# FPGA.net
KiCad netlist of a schematic drawn in Altium Designer
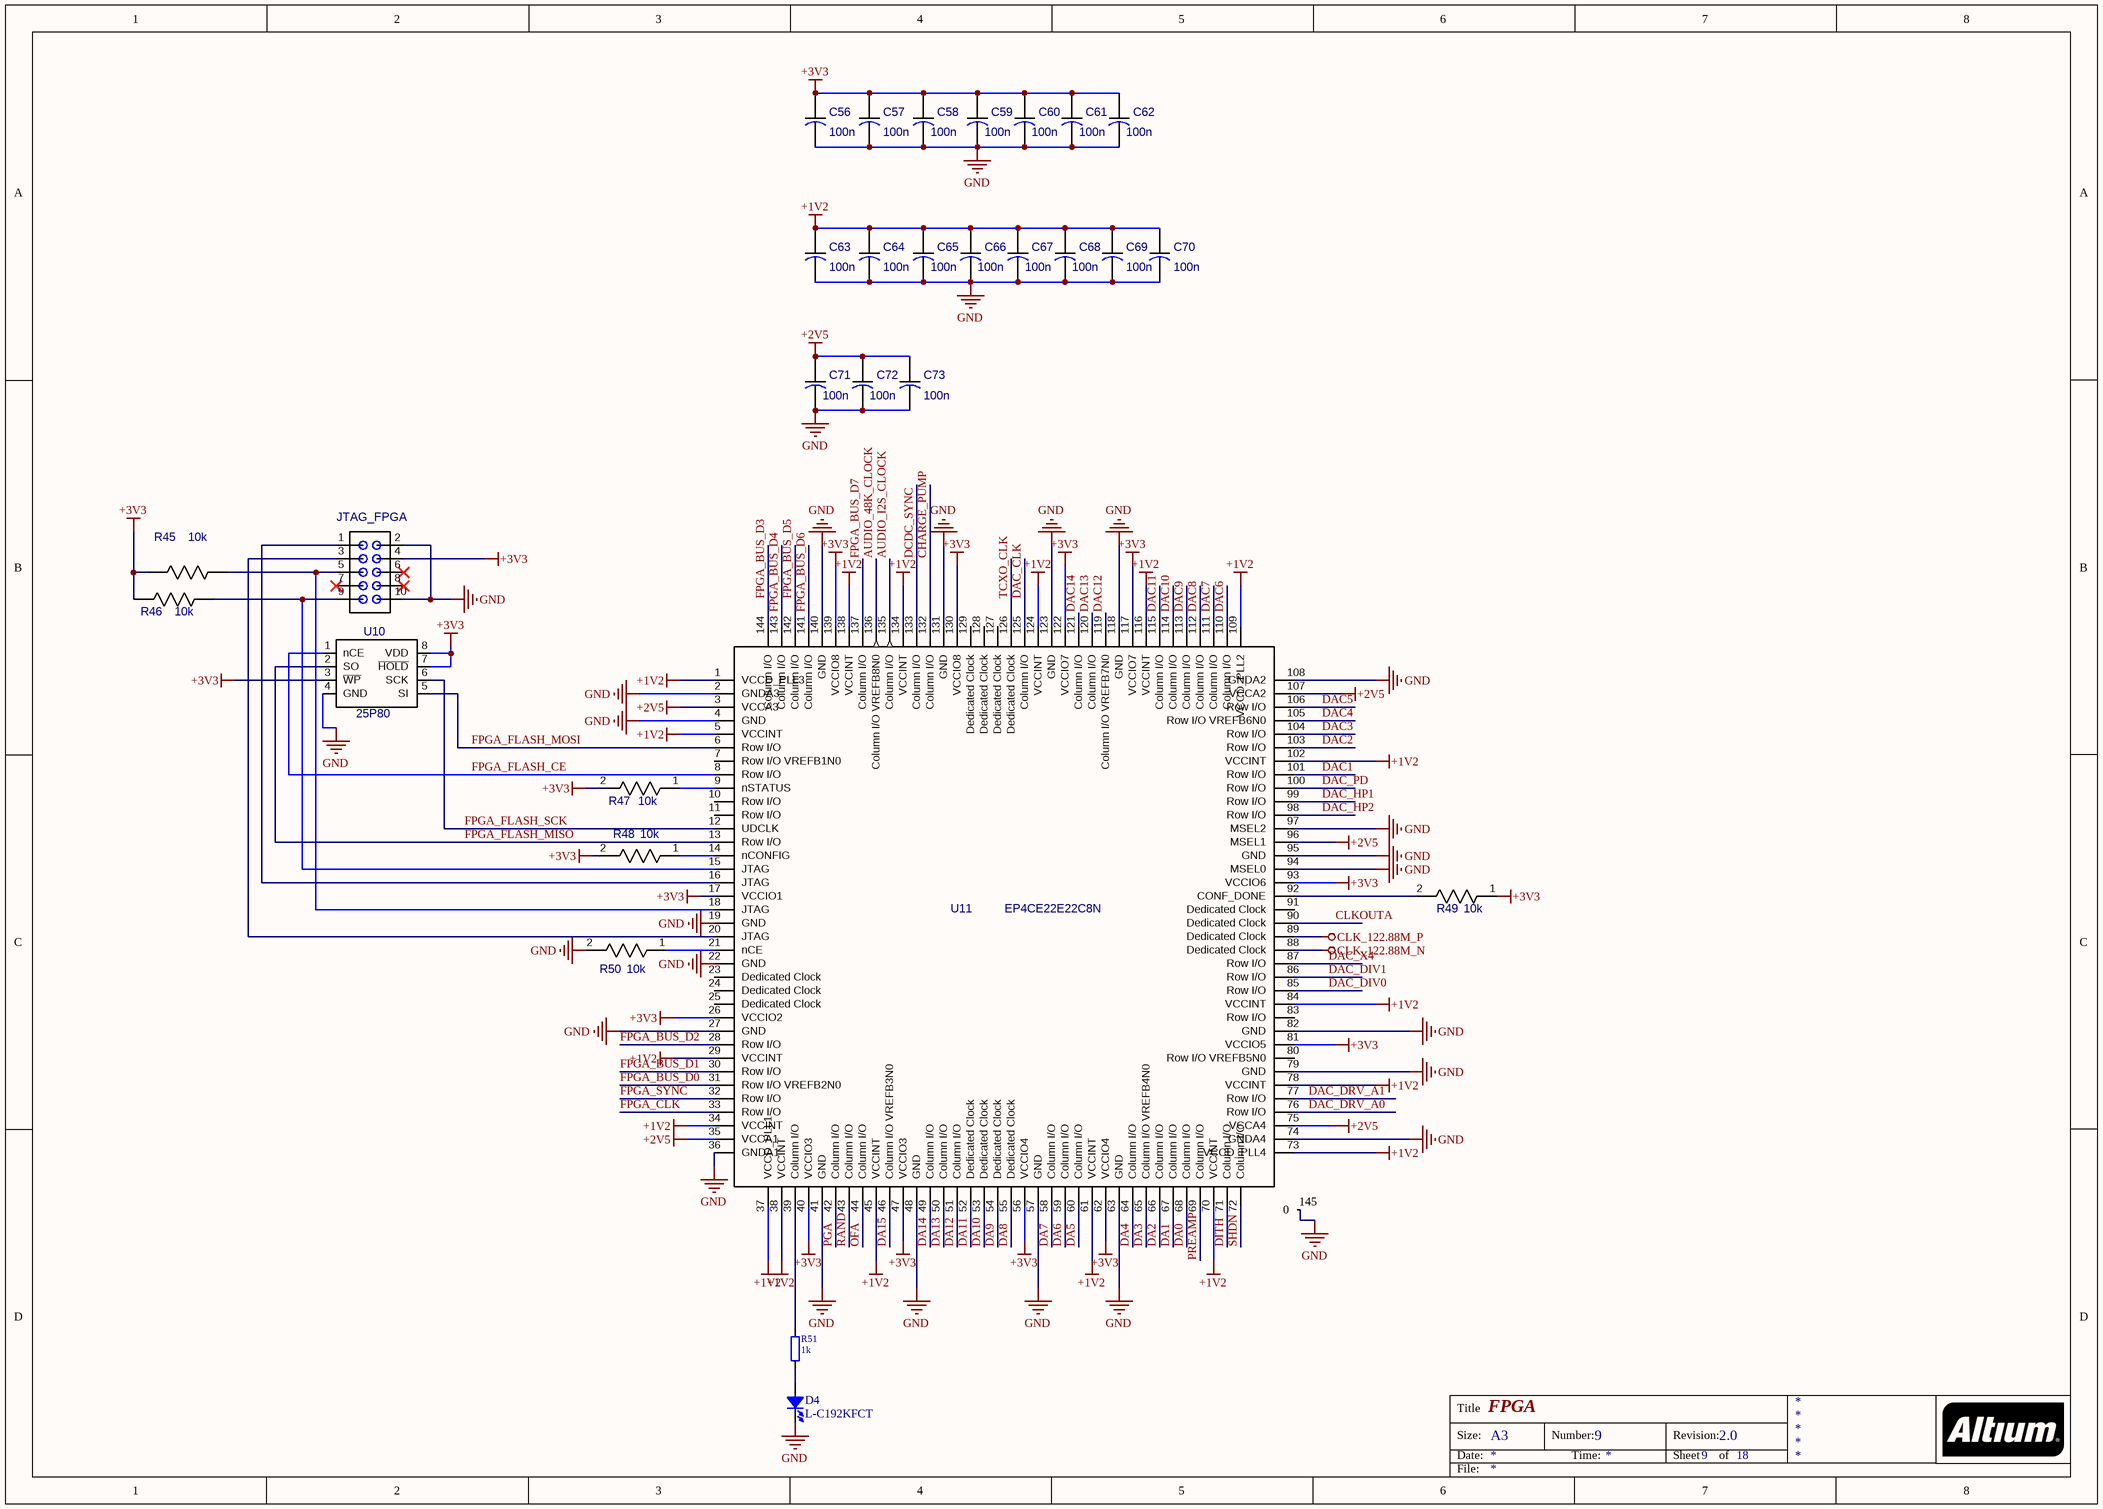
[diagram p0: FPGA.SchDoc]

(export (version "E")
  (design (tool "Eeschema 10.0.6"))
  (components
    (comp (ref "C56")
      (value "100n")
      (footprint "CAP_0805")
      (description "CAP_0805")
      (libsource (lib "*") (part "CAP_0805"))
    )
    (comp (ref "C57")
      (value "100n")
      (footprint "CAP_0805")
      (description "CAP_0805")
      (libsource (lib "*") (part "CAP_0805"))
    )
    (comp (ref "C58")
      (value "100n")
      (footprint "CAP_0805")
      (description "CAP_0805")
      (libsource (lib "*") (part "CAP_0805"))
    )
    (comp (ref "C59")
      (value "100n")
      (footprint "CAP_0805")
      (description "CAP_0805")
      (libsource (lib "*") (part "CAP_0805"))
    )
    (comp (ref "C60")
      (value "100n")
      (footprint "CAP_0805")
      (description "CAP_0805")
      (libsource (lib "*") (part "CAP_0805"))
    )
    (comp (ref "C61")
      (value "100n")
      (footprint "CAP_0805")
      (description "CAP_0805")
      (libsource (lib "*") (part "CAP_0805"))
    )
    (comp (ref "C62")
      (value "100n")
      (footprint "CAP_0805")
      (description "CAP_0805")
      (libsource (lib "*") (part "CAP_0805"))
    )
    (comp (ref "C63")
      (value "100n")
      (footprint "CAP_0805")
      (description "CAP_0805")
      (libsource (lib "*") (part "CAP_0805"))
    )
    (comp (ref "C64")
      (value "100n")
      (footprint "CAP_0805")
      (description "CAP_0805")
      (libsource (lib "*") (part "CAP_0805"))
    )
    (comp (ref "C65")
      (value "100n")
      (footprint "CAP_0805")
      (description "CAP_0805")
      (libsource (lib "*") (part "CAP_0805"))
    )
    (comp (ref "C66")
      (value "100n")
      (footprint "CAP_0805")
      (description "CAP_0805")
      (libsource (lib "*") (part "CAP_0805"))
    )
    (comp (ref "C67")
      (value "100n")
      (footprint "CAP_0805")
      (description "CAP_0805")
      (libsource (lib "*") (part "CAP_0805"))
    )
    (comp (ref "C68")
      (value "100n")
      (footprint "CAP_0805")
      (description "CAP_0805")
      (libsource (lib "*") (part "CAP_0805"))
    )
    (comp (ref "C69")
      (value "100n")
      (footprint "CAP_0805")
      (description "CAP_0805")
      (libsource (lib "*") (part "CAP_0805"))
    )
    (comp (ref "C70")
      (value "100n")
      (footprint "CAP_0805")
      (description "CAP_0805")
      (libsource (lib "*") (part "CAP_0805"))
    )
    (comp (ref "C71")
      (value "100n")
      (footprint "CAP_0805")
      (description "CAP_0805")
      (libsource (lib "*") (part "CAP_0805"))
    )
    (comp (ref "C72")
      (value "100n")
      (footprint "CAP_0805")
      (description "CAP_0805")
      (libsource (lib "*") (part "CAP_0805"))
    )
    (comp (ref "C73")
      (value "100n")
      (footprint "CAP_0805")
      (description "CAP_0805")
      (libsource (lib "*") (part "CAP_0805"))
    )
    (comp (ref "D4")
      (value "L-C192KFCT")
      (footprint "LED 0603")
      (description "SMD LED Diode")
      (fields (field (name "MANUFACTURER") "Paralight"))
      (libsource (lib "Hristo") (part "D LED"))
    )
    (comp (ref "JTAG_FPGA")
      (value "~")
      (footprint "IDC10")
      (description "2*5 Pin")
      (libsource (lib "*") (part "IDC10"))
    )
    (comp (ref "R45")
      (value "10k")
      (footprint "RES_0805")
      (description "RES_0805")
      (libsource (lib "") (part "RES_0805_1"))
    )
    (comp (ref "R46")
      (value "10k")
      (footprint "RES_0805")
      (description "RES_0805")
      (libsource (lib "") (part "RES_0805_1"))
    )
    (comp (ref "R47")
      (value "10k")
      (footprint "RES_0805")
      (description "RES_0805")
      (libsource (lib "*") (part "RES_0805"))
    )
    (comp (ref "R48")
      (value "10k")
      (footprint "RES_0805")
      (description "RES_0805")
      (libsource (lib "*") (part "RES_0805"))
    )
    (comp (ref "R49")
      (value "10k")
      (footprint "RES_0805")
      (description "RES_0805")
      (libsource (lib "*") (part "RES_0805"))
    )
    (comp (ref "R50")
      (value "10k")
      (footprint "RES_0805")
      (description "RES_0805")
      (libsource (lib "*") (part "RES_0805"))
    )
    (comp (ref "R51")
      (value "1k")
      (footprint "R-0603")
      (description "Chip Resistor")
      (fields (field (name "MANUFACTURER") "Yageo/Phycomp"))
      (libsource (lib "Hristo") (part "RES semi"))
    )
    (comp (ref "U10") (value "25P80") (footprint "25P80") (libsource (lib "*") (part "25P80")))
    (comp (ref "U11")
      (value "EP4CE22E22C8N")
      (footprint "QFP144-20-2222A")
      (libsource (lib "*") (part "EP4CE22E22C8N"))
    )
  )
  (nets
    (net (code "1") (name "+1V2") (class "Default")
      (node (ref "C63") (pin "1") (pinfunction "1_1") (pintype "passive"))
      (node (ref "C64") (pin "1") (pinfunction "1_1") (pintype "passive"))
      (node (ref "C65") (pin "1") (pinfunction "1_1") (pintype "passive"))
      (node (ref "C66") (pin "1") (pinfunction "1_1") (pintype "passive"))
      (node (ref "C67") (pin "1") (pinfunction "1_1") (pintype "passive"))
      (node (ref "C68") (pin "1") (pinfunction "1_1") (pintype "passive"))
      (node (ref "C69") (pin "1") (pinfunction "1_1") (pintype "passive"))
      (node (ref "C70") (pin "1") (pinfunction "1_1") (pintype "passive"))
      (node (ref "U11") (pin "1") (pinfunction "VCCD_PLL3_1") (pintype "passive"))
      (node (ref "U11") (pin "102") (pinfunction "VCCINT_102") (pintype "passive"))
      (node (ref "U11") (pin "109") (pinfunction "VCCD_PLL2_109") (pintype "passive"))
      (node (ref "U11") (pin "116") (pinfunction "VCCINT_116") (pintype "passive"))
      (node (ref "U11") (pin "124") (pinfunction "VCCINT_124") (pintype "passive"))
      (node (ref "U11") (pin "134") (pinfunction "VCCINT_134") (pintype "passive"))
      (node (ref "U11") (pin "138") (pinfunction "VCCINT_138") (pintype "passive"))
      (node (ref "U11") (pin "29") (pinfunction "VCCINT_29") (pintype "passive"))
      (node (ref "U11") (pin "34") (pinfunction "VCCINT_34") (pintype "passive"))
      (node (ref "U11") (pin "37") (pinfunction "VCCD_PLL1_37") (pintype "passive"))
      (node (ref "U11") (pin "38") (pinfunction "VCCINT_38") (pintype "passive"))
      (node (ref "U11") (pin "45") (pinfunction "VCCINT_45") (pintype "passive"))
      (node (ref "U11") (pin "5") (pinfunction "VCCINT_5") (pintype "passive"))
      (node (ref "U11") (pin "61") (pinfunction "VCCINT_61") (pintype "passive"))
      (node (ref "U11") (pin "70") (pinfunction "VCCINT_70") (pintype "passive"))
      (node (ref "U11") (pin "73") (pinfunction "VCCD_PLL4_73") (pintype "passive"))
      (node (ref "U11") (pin "78") (pinfunction "VCCINT_78") (pintype "passive"))
      (node (ref "U11") (pin "84") (pinfunction "VCCINT_84") (pintype "passive"))
    )
    (net (code "2") (name "+2V5") (class "Default")
      (node (ref "C71") (pin "1") (pinfunction "1_1") (pintype "passive"))
      (node (ref "C72") (pin "1") (pinfunction "1_1") (pintype "passive"))
      (node (ref "C73") (pin "1") (pinfunction "1_1") (pintype "passive"))
      (node (ref "U11") (pin "107") (pinfunction "VCCA2_107") (pintype "passive"))
      (node (ref "U11") (pin "3") (pinfunction "VCCA3_3") (pintype "passive"))
      (node (ref "U11") (pin "35") (pinfunction "VCCA1_35") (pintype "passive"))
      (node (ref "U11") (pin "75") (pinfunction "VCCA4_75") (pintype "passive"))
      (node (ref "U11") (pin "96") (pinfunction "MSEL1_96") (pintype "passive"))
    )
    (net (code "3") (name "+3V3") (class "Default")
      (node (ref "C56") (pin "1") (pinfunction "1_1") (pintype "passive"))
      (node (ref "C57") (pin "1") (pinfunction "1_1") (pintype "passive"))
      (node (ref "C58") (pin "1") (pinfunction "1_1") (pintype "passive"))
      (node (ref "C59") (pin "1") (pinfunction "1_1") (pintype "passive"))
      (node (ref "C60") (pin "1") (pinfunction "1_1") (pintype "passive"))
      (node (ref "C61") (pin "1") (pinfunction "1_1") (pintype "passive"))
      (node (ref "C62") (pin "1") (pinfunction "1_1") (pintype "passive"))
      (node (ref "JTAG_FPGA") (pin "4") (pinfunction "4_4") (pintype "passive"))
      (node (ref "R45") (pin "2") (pinfunction "2_2") (pintype "passive"))
      (node (ref "R46") (pin "2") (pinfunction "2_2") (pintype "passive"))
      (node (ref "R47") (pin "2") (pinfunction "2_2") (pintype "passive"))
      (node (ref "R48") (pin "2") (pinfunction "2_2") (pintype "passive"))
      (node (ref "R49") (pin "1") (pinfunction "1_1") (pintype "passive"))
      (node (ref "U10") (pin "3") (pinfunction "~{WP}_3") (pintype "passive"))
      (node (ref "U10") (pin "7") (pinfunction "~{HOLD}_7") (pintype "passive"))
      (node (ref "U10") (pin "8") (pinfunction "VDD_8") (pintype "passive"))
      (node (ref "U11") (pin "117") (pinfunction "VCCIO7_117") (pintype "passive"))
      (node (ref "U11") (pin "122") (pinfunction "VCCIO7_122") (pintype "passive"))
      (node (ref "U11") (pin "130") (pinfunction "VCCIO8_130") (pintype "passive"))
      (node (ref "U11") (pin "139") (pinfunction "VCCIO8_139") (pintype "passive"))
      (node (ref "U11") (pin "17") (pinfunction "VCCIO1_17") (pintype "passive"))
      (node (ref "U11") (pin "26") (pinfunction "VCCIO2_26") (pintype "passive"))
      (node (ref "U11") (pin "40") (pinfunction "VCCIO3_40") (pintype "passive"))
      (node (ref "U11") (pin "47") (pinfunction "VCCIO3_47") (pintype "passive"))
      (node (ref "U11") (pin "56") (pinfunction "VCCIO4_56") (pintype "passive"))
      (node (ref "U11") (pin "62") (pinfunction "VCCIO4_62") (pintype "passive"))
      (node (ref "U11") (pin "81") (pinfunction "VCCIO5_81") (pintype "passive"))
      (node (ref "U11") (pin "93") (pinfunction "VCCIO6_93") (pintype "passive"))
    )
    (net (code "4") (name "/AUDIO_48K_CLOCK") (class "Default")
      (node (ref "U11") (pin "136") (pinfunction "Column_I/O_VREFB8N0_136") (pintype "output"))
    )
    (net (code "5") (name "/AUDIO_I2S_CLOCK") (class "Default")
      (node (ref "U11") (pin "135") (pinfunction "Column_I/O_135") (pintype "output"))
    )
    (net (code "6") (name "/CHARGE_PUMP") (class "Default")
      (node (ref "U11") (pin "132") (pinfunction "Column_I/O_132") (pintype "passive"))
    )
    (net (code "7") (name "/CLKOUTA") (class "Default")
      (node (ref "U11") (pin "90") (pinfunction "Dedicated_Clock_90") (pintype "passive"))
    )
    (net (code "8") (name "/DA0") (class "Default")
      (node (ref "U11") (pin "68") (pinfunction "Column_I/O_68") (pintype "passive"))
    )
    (net (code "9") (name "/DA1") (class "Default")
      (node (ref "U11") (pin "67") (pinfunction "Column_I/O_67") (pintype "passive"))
    )
    (net (code "10") (name "/DA2") (class "Default")
      (node (ref "U11") (pin "66") (pinfunction "Column_I/O_66") (pintype "passive"))
    )
    (net (code "11") (name "/DA3") (class "Default")
      (node (ref "U11") (pin "65") (pinfunction "Column_I/O_VREFB4N0_65") (pintype "passive"))
    )
    (net (code "12") (name "/DA4") (class "Default")
      (node (ref "U11") (pin "64") (pinfunction "Column_I/O_64") (pintype "passive"))
    )
    (net (code "13") (name "/DA5") (class "Default")
      (node (ref "U11") (pin "60") (pinfunction "Column_I/O_60") (pintype "passive"))
    )
    (net (code "14") (name "/DA6") (class "Default")
      (node (ref "U11") (pin "59") (pinfunction "Column_I/O_59") (pintype "passive"))
    )
    (net (code "15") (name "/DA7") (class "Default")
      (node (ref "U11") (pin "58") (pinfunction "Column_I/O_58") (pintype "passive"))
    )
    (net (code "16") (name "/DA8") (class "Default")
      (node (ref "U11") (pin "55") (pinfunction "Dedicated_Clock_55") (pintype "passive"))
    )
    (net (code "17") (name "/DA9") (class "Default")
      (node (ref "U11") (pin "54") (pinfunction "Dedicated_Clock_54") (pintype "passive"))
    )
    (net (code "18") (name "/DA10") (class "Default")
      (node (ref "U11") (pin "53") (pinfunction "Dedicated_Clock_53") (pintype "passive"))
    )
    (net (code "19") (name "/DA11") (class "Default")
      (node (ref "U11") (pin "52") (pinfunction "Dedicated_Clock_52") (pintype "passive"))
    )
    (net (code "20") (name "/DA12") (class "Default")
      (node (ref "U11") (pin "51") (pinfunction "Column_I/O_51") (pintype "passive"))
    )
    (net (code "21") (name "/DA13") (class "Default")
      (node (ref "U11") (pin "50") (pinfunction "Column_I/O_50") (pintype "passive"))
    )
    (net (code "22") (name "/DA14") (class "Default")
      (node (ref "U11") (pin "49") (pinfunction "Column_I/O_49") (pintype "passive"))
    )
    (net (code "23") (name "/DA15") (class "Default")
      (node (ref "U11") (pin "46") (pinfunction "Column_I/O_VREFB3N0_46") (pintype "passive"))
    )
    (net (code "24") (name "/DAC1") (class "Default")
      (node (ref "U11") (pin "101") (pinfunction "Row_I/O_101") (pintype "passive"))
    )
    (net (code "25") (name "/DAC2") (class "Default")
      (node (ref "U11") (pin "103") (pinfunction "Row_I/O_103") (pintype "passive"))
    )
    (net (code "26") (name "/DAC3") (class "Default")
      (node (ref "U11") (pin "104") (pinfunction "Row_I/O_104") (pintype "passive"))
    )
    (net (code "27") (name "/DAC4") (class "Default")
      (node (ref "U11") (pin "105") (pinfunction "Row_I/O_VREFB6N0_105") (pintype "passive"))
    )
    (net (code "28") (name "/DAC5") (class "Default")
      (node (ref "U11") (pin "106") (pinfunction "Row_I/O_106") (pintype "passive"))
    )
    (net (code "29") (name "/DAC6") (class "Default")
      (node (ref "U11") (pin "110") (pinfunction "Column_I/O_110") (pintype "passive"))
    )
    (net (code "30") (name "/DAC7") (class "Default")
      (node (ref "U11") (pin "111") (pinfunction "Column_I/O_111") (pintype "passive"))
    )
    (net (code "31") (name "/DAC8") (class "Default")
      (node (ref "U11") (pin "112") (pinfunction "Column_I/O_112") (pintype "passive"))
    )
    (net (code "32") (name "/DAC9") (class "Default")
      (node (ref "U11") (pin "113") (pinfunction "Column_I/O_113") (pintype "passive"))
    )
    (net (code "33") (name "/DAC10") (class "Default")
      (node (ref "U11") (pin "114") (pinfunction "Column_I/O_114") (pintype "passive"))
    )
    (net (code "34") (name "/DAC11") (class "Default")
      (node (ref "U11") (pin "115") (pinfunction "Column_I/O_115") (pintype "passive"))
    )
    (net (code "35") (name "/DAC12") (class "Default")
      (node (ref "U11") (pin "119") (pinfunction "Column_I/O_VREFB7N0_119") (pintype "passive"))
    )
    (net (code "36") (name "/DAC13") (class "Default")
      (node (ref "U11") (pin "120") (pinfunction "Column_I/O_120") (pintype "passive"))
    )
    (net (code "37") (name "/DAC14") (class "Default")
      (node (ref "U11") (pin "121") (pinfunction "Column_I/O_121") (pintype "passive"))
    )
    (net (code "38") (name "/DAC_CLK") (class "Default")
      (node (ref "U11") (pin "125") (pinfunction "Column_I/O_125") (pintype "passive"))
    )
    (net (code "39") (name "/DAC_DIV0") (class "Default")
      (node (ref "U11") (pin "85") (pinfunction "Row_I/O_85") (pintype "passive"))
    )
    (net (code "40") (name "/DAC_DIV1") (class "Default")
      (node (ref "U11") (pin "86") (pinfunction "Row_I/O_86") (pintype "passive"))
    )
    (net (code "41") (name "/DAC_DRV_A0") (class "Default")
      (node (ref "U11") (pin "76") (pinfunction "Row_I/O_76") (pintype "passive"))
    )
    (net (code "42") (name "/DAC_DRV_A1") (class "Default")
      (node (ref "U11") (pin "77") (pinfunction "Row_I/O_77") (pintype "passive"))
    )
    (net (code "43") (name "/DAC_HP1") (class "Default")
      (node (ref "U11") (pin "99") (pinfunction "Row_I/O_99") (pintype "passive"))
    )
    (net (code "44") (name "/DAC_HP2") (class "Default")
      (node (ref "U11") (pin "98") (pinfunction "Row_I/O_98") (pintype "passive"))
    )
    (net (code "45") (name "/DAC_PD") (class "Default")
      (node (ref "U11") (pin "100") (pinfunction "Row_I/O_100") (pintype "passive"))
    )
    (net (code "46") (name "/DAC_X4") (class "Default")
      (node (ref "U11") (pin "87") (pinfunction "Row_I/O_87") (pintype "passive"))
    )
    (net (code "47") (name "/DCDC_SYNC") (class "Default")
      (node (ref "U11") (pin "133") (pinfunction "Column_I/O_133") (pintype "passive"))
    )
    (net (code "48") (name "/DITH") (class "Default")
      (node (ref "U11") (pin "71") (pinfunction "Column_I/O_71") (pintype "passive"))
    )
    (net (code "49") (name "/FPGA_BUS_D0") (class "Default")
      (node (ref "U11") (pin "31") (pinfunction "Row_I/O_VREFB2N0_31") (pintype "passive"))
    )
    (net (code "50") (name "/FPGA_BUS_D1") (class "Default")
      (node (ref "U11") (pin "30") (pinfunction "Row_I/O_30") (pintype "passive"))
    )
    (net (code "51") (name "/FPGA_BUS_D2") (class "Default")
      (node (ref "U11") (pin "28") (pinfunction "Row_I/O_28") (pintype "passive"))
    )
    (net (code "52") (name "/FPGA_BUS_D3") (class "Default")
      (node (ref "U11") (pin "144") (pinfunction "Column_I/O_144") (pintype "passive"))
    )
    (net (code "53") (name "/FPGA_BUS_D4") (class "Default")
      (node (ref "U11") (pin "143") (pinfunction "Column_I/O_143") (pintype "passive"))
    )
    (net (code "54") (name "/FPGA_BUS_D5") (class "Default")
      (node (ref "U11") (pin "142") (pinfunction "Column_I/O_142") (pintype "passive"))
    )
    (net (code "55") (name "/FPGA_BUS_D6") (class "Default")
      (node (ref "U11") (pin "141") (pinfunction "Column_I/O_141") (pintype "passive"))
    )
    (net (code "56") (name "/FPGA_BUS_D7") (class "Default")
      (node (ref "U11") (pin "137") (pinfunction "Column_I/O_137") (pintype "passive"))
    )
    (net (code "57") (name "/FPGA_CLK") (class "Default")
      (node (ref "U11") (pin "33") (pinfunction "Row_I/O_33") (pintype "passive"))
    )
    (net (code "58") (name "/FPGA_FLASH_CE") (class "Default")
      (node (ref "U10") (pin "1") (pinfunction "nCE_1") (pintype "passive"))
      (node (ref "U11") (pin "8") (pinfunction "Row_I/O_8") (pintype "passive"))
    )
    (net (code "59") (name "/FPGA_FLASH_MISO") (class "Default")
      (node (ref "U10") (pin "2") (pinfunction "SO_2") (pintype "passive"))
      (node (ref "U11") (pin "13") (pinfunction "Row_I/O_13") (pintype "passive"))
    )
    (net (code "60") (name "/FPGA_FLASH_MOSI") (class "Default")
      (node (ref "U10") (pin "5") (pinfunction "SI_5") (pintype "passive"))
      (node (ref "U11") (pin "6") (pinfunction "Row_I/O_6") (pintype "passive"))
    )
    (net (code "61") (name "/FPGA_FLASH_SCK") (class "Default")
      (node (ref "U10") (pin "6") (pinfunction "SCK_6") (pintype "passive"))
      (node (ref "U11") (pin "12") (pinfunction "UDCLK_12") (pintype "passive"))
    )
    (net (code "62") (name "/FPGA_SYNC") (class "Default")
      (node (ref "U11") (pin "32") (pinfunction "Row_I/O_32") (pintype "passive"))
    )
    (net (code "63") (name "/OFA") (class "Default")
      (node (ref "U11") (pin "44") (pinfunction "Column_I/O_44") (pintype "passive"))
    )
    (net (code "64") (name "/PGA") (class "Default")
      (node (ref "U11") (pin "42") (pinfunction "Column_I/O_42") (pintype "passive"))
    )
    (net (code "65") (name "/PREAMP") (class "Default")
      (node (ref "U11") (pin "69") (pinfunction "Column_I/O_69") (pintype "passive"))
    )
    (net (code "66") (name "/RAND") (class "Default")
      (node (ref "U11") (pin "43") (pinfunction "Column_I/O_43") (pintype "passive"))
    )
    (net (code "67") (name "/SHDN") (class "Default")
      (node (ref "U11") (pin "72") (pinfunction "Column_I/O_72") (pintype "passive"))
    )
    (net (code "68") (name "/TCXO_CLK") (class "Default")
      (node (ref "U11") (pin "126") (pinfunction "Dedicated_Clock_126") (pintype "passive"))
    )
    (net (code "69") (name "CLK_122.88M_N") (class "Default")
      (node (ref "U11") (pin "88") (pinfunction "Dedicated_Clock_88") (pintype "passive"))
    )
    (net (code "70") (name "CLK_122.88M_P") (class "Default")
      (node (ref "U11") (pin "89") (pinfunction "Dedicated_Clock_89") (pintype "passive"))
    )
    (net (code "71") (name "GND") (class "Default")
      (node (ref "C56") (pin "2") (pinfunction "2_2") (pintype "passive"))
      (node (ref "C57") (pin "2") (pinfunction "2_2") (pintype "passive"))
      (node (ref "C58") (pin "2") (pinfunction "2_2") (pintype "passive"))
      (node (ref "C59") (pin "2") (pinfunction "2_2") (pintype "passive"))
      (node (ref "C60") (pin "2") (pinfunction "2_2") (pintype "passive"))
      (node (ref "C61") (pin "2") (pinfunction "2_2") (pintype "passive"))
      (node (ref "C62") (pin "2") (pinfunction "2_2") (pintype "passive"))
      (node (ref "C63") (pin "2") (pinfunction "2_2") (pintype "passive"))
      (node (ref "C64") (pin "2") (pinfunction "2_2") (pintype "passive"))
      (node (ref "C65") (pin "2") (pinfunction "2_2") (pintype "passive"))
      (node (ref "C66") (pin "2") (pinfunction "2_2") (pintype "passive"))
      (node (ref "C67") (pin "2") (pinfunction "2_2") (pintype "passive"))
      (node (ref "C68") (pin "2") (pinfunction "2_2") (pintype "passive"))
      (node (ref "C69") (pin "2") (pinfunction "2_2") (pintype "passive"))
      (node (ref "C70") (pin "2") (pinfunction "2_2") (pintype "passive"))
      (node (ref "C71") (pin "2") (pinfunction "2_2") (pintype "passive"))
      (node (ref "C72") (pin "2") (pinfunction "2_2") (pintype "passive"))
      (node (ref "C73") (pin "2") (pinfunction "2_2") (pintype "passive"))
      (node (ref "D4") (pin "2") (pintype "passive"))
      (node (ref "JTAG_FPGA") (pin "10") (pinfunction "10_10") (pintype "passive"))
      (node (ref "JTAG_FPGA") (pin "2") (pinfunction "2_2") (pintype "passive"))
      (node (ref "R50") (pin "2") (pinfunction "2_2") (pintype "passive"))
      (node (ref "U10") (pin "4") (pinfunction "GND_4") (pintype "passive"))
      (node (ref "U11") (pin "108") (pinfunction "GNDA2_108") (pintype "passive"))
      (node (ref "U11") (pin "118") (pinfunction "GND_118") (pintype "passive"))
      (node (ref "U11") (pin "123") (pinfunction "GND_123") (pintype "passive"))
      (node (ref "U11") (pin "131") (pinfunction "GND_131") (pintype "passive"))
      (node (ref "U11") (pin "140") (pinfunction "GND_140") (pintype "passive"))
      (node (ref "U11") (pin "145") (pinfunction "0_145") (pintype "passive"))
      (node (ref "U11") (pin "19") (pinfunction "GND_19") (pintype "passive"))
      (node (ref "U11") (pin "2") (pinfunction "GNDA3_2") (pintype "passive"))
      (node (ref "U11") (pin "22") (pinfunction "GND_22") (pintype "passive"))
      (node (ref "U11") (pin "27") (pinfunction "GND_27") (pintype "passive"))
      (node (ref "U11") (pin "36") (pinfunction "GNDA1_36") (pintype "passive"))
      (node (ref "U11") (pin "4") (pinfunction "GND_4") (pintype "passive"))
      (node (ref "U11") (pin "41") (pinfunction "GND_41") (pintype "passive"))
      (node (ref "U11") (pin "48") (pinfunction "GND_48") (pintype "passive"))
      (node (ref "U11") (pin "57") (pinfunction "GND_57") (pintype "passive"))
      (node (ref "U11") (pin "63") (pinfunction "GND_63") (pintype "passive"))
      (node (ref "U11") (pin "74") (pinfunction "GNDA4_74") (pintype "passive"))
      (node (ref "U11") (pin "79") (pinfunction "GND_79") (pintype "passive"))
      (node (ref "U11") (pin "82") (pinfunction "GND_82") (pintype "passive"))
      (node (ref "U11") (pin "94") (pinfunction "MSEL0_94") (pintype "passive"))
      (node (ref "U11") (pin "95") (pinfunction "GND_95") (pintype "passive"))
      (node (ref "U11") (pin "97") (pinfunction "MSEL2_97") (pintype "passive"))
    )
    (net (code "72") (name "Net-(D4-Pad1)") (class "Default")
      (node (ref "D4") (pin "1") (pintype "passive"))
      (node (ref "R51") (pin "1") (pinfunction "1_1") (pintype "passive"))
    )
    (net (code "73") (name "Net-(JTAG_FPGA-Pad1)") (class "Default")
      (node (ref "JTAG_FPGA") (pin "1") (pinfunction "1_1") (pintype "passive"))
      (node (ref "U11") (pin "16") (pinfunction "JTAG_16") (pintype "passive"))
    )
    (net (code "74") (name "Net-(JTAG_FPGA-Pad3)") (class "Default")
      (node (ref "JTAG_FPGA") (pin "3") (pinfunction "3_3") (pintype "passive"))
      (node (ref "U11") (pin "20") (pinfunction "JTAG_20") (pintype "passive"))
    )
    (net (code "75") (name "Net-(JTAG_FPGA-Pad5)") (class "Default")
      (node (ref "JTAG_FPGA") (pin "5") (pinfunction "5_5") (pintype "passive"))
      (node (ref "R45") (pin "1") (pinfunction "1_1") (pintype "passive"))
      (node (ref "U11") (pin "18") (pinfunction "JTAG_18") (pintype "passive"))
    )
    (net (code "76") (name "Net-(JTAG_FPGA-Pad9)") (class "Default")
      (node (ref "JTAG_FPGA") (pin "9") (pinfunction "9_9") (pintype "passive"))
      (node (ref "R46") (pin "1") (pinfunction "1_1") (pintype "passive"))
      (node (ref "U11") (pin "15") (pinfunction "JTAG_15") (pintype "passive"))
    )
    (net (code "77") (name "Net-(R51-Pad2)") (class "Default")
      (node (ref "R51") (pin "2") (pinfunction "2_2") (pintype "passive"))
      (node (ref "U11") (pin "39") (pinfunction "Column_I/O_39") (pintype "passive"))
    )
    (net (code "78") (name "Net-(U11-CONF_DONE)") (class "Default")
      (node (ref "R49") (pin "2") (pinfunction "2_2") (pintype "passive"))
      (node (ref "U11") (pin "92") (pinfunction "CONF_DONE_92") (pintype "passive"))
    )
    (net (code "79") (name "Net-(U11-nCE)") (class "Default")
      (node (ref "R50") (pin "1") (pinfunction "1_1") (pintype "passive"))
      (node (ref "U11") (pin "21") (pinfunction "nCE_21") (pintype "passive"))
    )
    (net (code "80") (name "Net-(U11-nCONFIG)") (class "Default")
      (node (ref "R48") (pin "1") (pinfunction "1_1") (pintype "passive"))
      (node (ref "U11") (pin "14") (pinfunction "nCONFIG_14") (pintype "passive"))
    )
    (net (code "81") (name "Net-(U11-nSTATUS)") (class "Default")
      (node (ref "R47") (pin "1") (pinfunction "1_1") (pintype "passive"))
      (node (ref "U11") (pin "9") (pinfunction "nSTATUS_9") (pintype "passive"))
    )
    (net (code "82") (name "unconnected-(JTAG_FPGA-Pad6)") (class "Default")
      (node (ref "JTAG_FPGA") (pin "6") (pinfunction "6_6") (pintype "passive+no_connect"))
    )
    (net (code "83") (name "unconnected-(JTAG_FPGA-Pad7)") (class "Default")
      (node (ref "JTAG_FPGA") (pin "7") (pinfunction "7_7") (pintype "passive+no_connect"))
    )
    (net (code "84") (name "unconnected-(JTAG_FPGA-Pad8)") (class "Default")
      (node (ref "JTAG_FPGA") (pin "8") (pinfunction "8_8") (pintype "passive+no_connect"))
    )
    (net (code "85") (name "unconnected-(U11-Dedicated_Clock-Pad23)") (class "Default")
      (node (ref "U11") (pin "23") (pinfunction "Dedicated_Clock_23") (pintype "passive"))
    )
    (net (code "86") (name "unconnected-(U11-Dedicated_Clock-Pad24)") (class "Default")
      (node (ref "U11") (pin "24") (pinfunction "Dedicated_Clock_24") (pintype "passive"))
    )
    (net (code "87") (name "unconnected-(U11-Dedicated_Clock-Pad25)") (class "Default")
      (node (ref "U11") (pin "25") (pinfunction "Dedicated_Clock_25") (pintype "passive"))
    )
    (net (code "88") (name "unconnected-(U11-Dedicated_Clock-Pad91)") (class "Default")
      (node (ref "U11") (pin "91") (pinfunction "Dedicated_Clock_91") (pintype "passive"))
    )
    (net (code "89") (name "unconnected-(U11-Dedicated_Clock-Pad127)") (class "Default")
      (node (ref "U11") (pin "127") (pinfunction "Dedicated_Clock_127") (pintype "passive"))
    )
    (net (code "90") (name "unconnected-(U11-Dedicated_Clock-Pad128)") (class "Default")
      (node (ref "U11") (pin "128") (pinfunction "Dedicated_Clock_128") (pintype "passive"))
    )
    (net (code "91") (name "unconnected-(U11-Dedicated_Clock-Pad129)") (class "Default")
      (node (ref "U11") (pin "129") (pinfunction "Dedicated_Clock_129") (pintype "passive"))
    )
    (net (code "92") (name "unconnected-(U11-Row_I{slash}O-Pad10)") (class "Default")
      (node (ref "U11") (pin "10") (pinfunction "Row_I/O_10") (pintype "passive"))
    )
    (net (code "93") (name "unconnected-(U11-Row_I{slash}O-Pad11)") (class "Default")
      (node (ref "U11") (pin "11") (pinfunction "Row_I/O_11") (pintype "passive"))
    )
    (net (code "94") (name "unconnected-(U11-Row_I{slash}O-Pad83)") (class "Default")
      (node (ref "U11") (pin "83") (pinfunction "Row_I/O_83") (pintype "passive"))
    )
    (net (code "95") (name "unconnected-(U11-Row_I{slash}O_VREFB1N0-Pad7)") (class "Default")
      (node (ref "U11") (pin "7") (pinfunction "Row_I/O_VREFB1N0_7") (pintype "passive"))
    )
    (net (code "96") (name "unconnected-(U11-Row_I{slash}O_VREFB5N0-Pad80)") (class "Default")
      (node (ref "U11") (pin "80") (pinfunction "Row_I/O_VREFB5N0_80") (pintype "passive"))
    )
  )
)
